# untitled_revisi.net
KiCad netlist of a schematic drawn in EAGLE
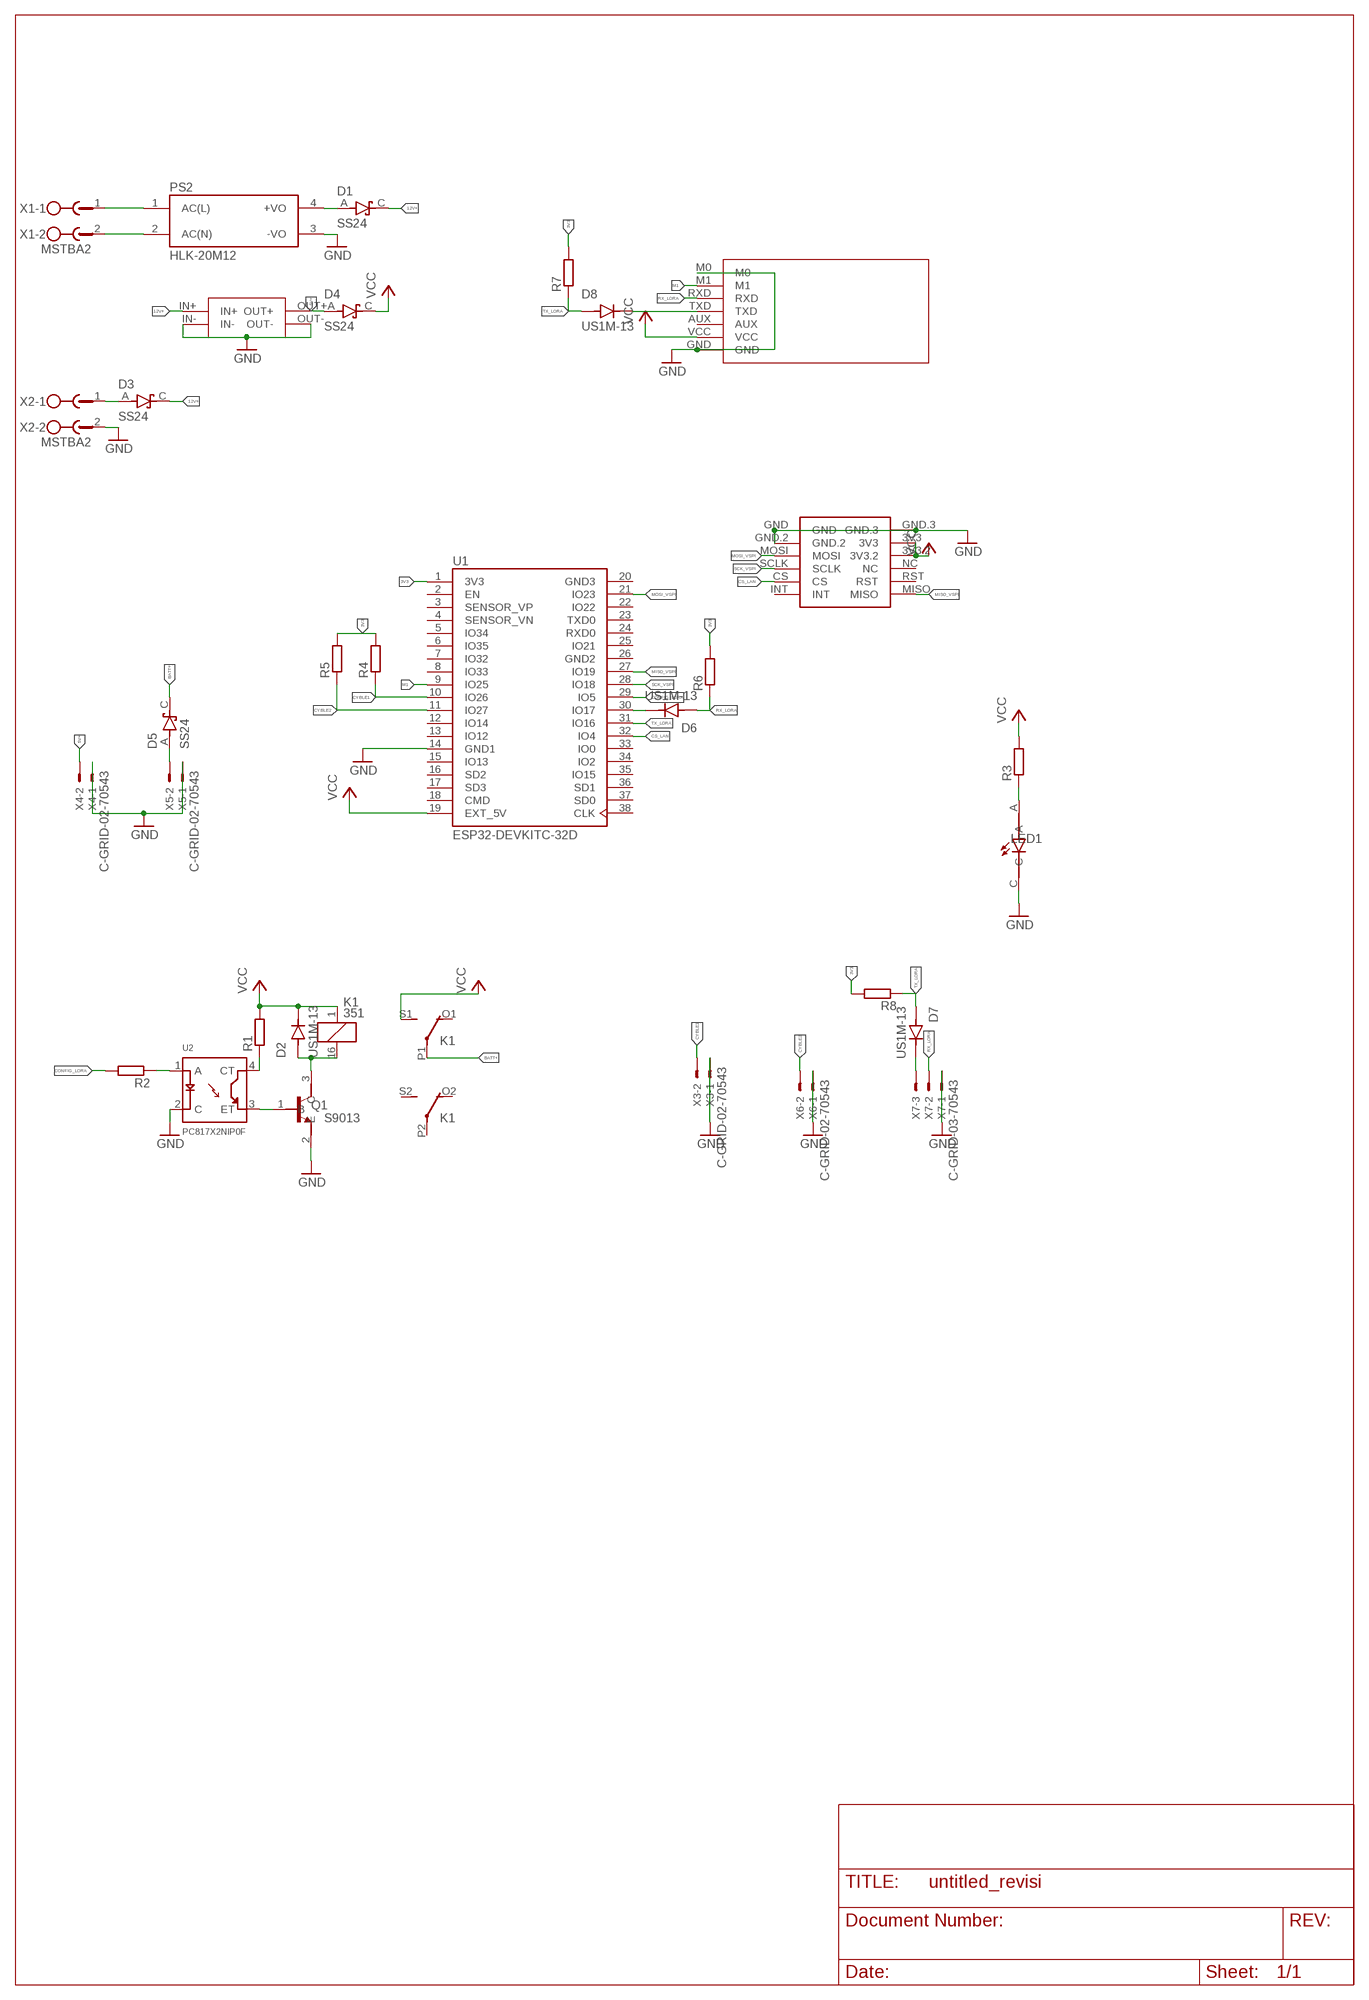
[diagram p0: schematic, sheet 1]

(export (version "E")
  (design (tool "Eeschema 10.0.6"))
  (components
    (comp (ref "D1")
      (value "SS24")
      (footprint "eagle-import:DIOM5336X265N")
      (fields (field (name "MF") "ON Semiconductor"))
      (libsource (lib "eagle-import") (part "SS24"))
    )
    (comp (ref "D2")
      (value "US1M-13")
      (footprint "eagle-import:DIOM5226X240N")
      (fields (field (name "MF") "Diodes Incorporated"))
      (libsource (lib "eagle-import") (part "US1M-13"))
    )
    (comp (ref "D3")
      (value "SS24")
      (footprint "eagle-import:DIOM5336X265N")
      (fields (field (name "MF") "ON Semiconductor"))
      (libsource (lib "eagle-import") (part "SS24"))
    )
    (comp (ref "D4")
      (value "SS24")
      (footprint "eagle-import:DIOM5336X265N")
      (fields (field (name "MF") "ON Semiconductor"))
      (libsource (lib "eagle-import") (part "SS24"))
    )
    (comp (ref "D5")
      (value "SS24")
      (footprint "eagle-import:DIOM5336X265N")
      (fields (field (name "MF") "ON Semiconductor"))
      (libsource (lib "eagle-import") (part "SS24"))
    )
    (comp (ref "D6")
      (value "US1M-13")
      (footprint "eagle-import:DIOM5226X240N")
      (fields (field (name "MF") "Diodes Incorporated"))
      (libsource (lib "eagle-import") (part "US1M-13"))
    )
    (comp (ref "D7")
      (value "US1M-13")
      (footprint "eagle-import:DIOM5226X240N")
      (fields (field (name "MF") "Diodes Incorporated"))
      (libsource (lib "eagle-import") (part "US1M-13"))
    )
    (comp (ref "D8")
      (value "US1M-13")
      (footprint "eagle-import:DIOM5226X240N")
      (fields (field (name "MF") "Diodes Incorporated"))
      (libsource (lib "eagle-import") (part "US1M-13"))
    )
    (comp (ref "EBYTEE220-900T22D1")
      (value "EBYTEE220-900T22D")
      (footprint "eagle-import:EBYTEE220-900T22D")
      (libsource (lib "eagle-import") (part "EBYTEE220-900T22D"))
    )
    (comp (ref "K1")
      (value "351")
      (footprint "eagle-import:351")
      (libsource (lib "eagle-import") (part "351"))
    )
    (comp (ref "LED1")
      (value "SML-LXT0805IW-TR")
      (footprint "eagle-import:LEDC2012X120N")
      (fields (field (name "MF") "Lumex Opto/Components"))
      (libsource (lib "eagle-import") (part "SML-LXT0805IW-TR"))
    )
    (comp (ref "MINI1")
      (value "MINI560")
      (footprint "eagle-import:MINI560")
      (libsource (lib "eagle-import") (part "MINI560"))
    )
    (comp (ref "PS2")
      (value "HLK-20M12")
      (footprint "eagle-import:CONV_HLK-20M12")
      (fields (field (name "MF") "Hi-link"))
      (libsource (lib "eagle-import") (part "HLK-20M12"))
    )
    (comp (ref "Q1")
      (value "S9013")
      (footprint "eagle-import:SOT95P240X120-3N")
      (fields (field (name "MF") "JCET"))
      (libsource (lib "eagle-import") (part "S9013"))
    )
    (comp (ref "R1")
      (value "R-EU_R0805")
      (footprint "eagle-import:R0805")
      (libsource (lib "eagle-import") (part "R-EU_R0805"))
    )
    (comp (ref "R2")
      (value "R-EU_R0805")
      (footprint "eagle-import:R0805")
      (libsource (lib "eagle-import") (part "R-EU_R0805"))
    )
    (comp (ref "R3")
      (value "R-EU_R0805")
      (footprint "eagle-import:R0805")
      (libsource (lib "eagle-import") (part "R-EU_R0805"))
    )
    (comp (ref "R4")
      (value "R-EU_R0805")
      (footprint "eagle-import:R0805")
      (libsource (lib "eagle-import") (part "R-EU_R0805"))
    )
    (comp (ref "R5")
      (value "R-EU_R0805")
      (footprint "eagle-import:R0805")
      (libsource (lib "eagle-import") (part "R-EU_R0805"))
    )
    (comp (ref "R6")
      (value "R-EU_R0805")
      (footprint "eagle-import:R0805")
      (libsource (lib "eagle-import") (part "R-EU_R0805"))
    )
    (comp (ref "R7")
      (value "R-EU_R0805")
      (footprint "eagle-import:R0805")
      (libsource (lib "eagle-import") (part "R-EU_R0805"))
    )
    (comp (ref "R8")
      (value "R-EU_R0805")
      (footprint "eagle-import:R0805")
      (libsource (lib "eagle-import") (part "R-EU_R0805"))
    )
    (comp (ref "U$1")
      (value "MINI_W5500")
      (footprint "eagle-import:MINI_W5500")
      (libsource (lib "eagle-import") (part "MINI_W5500"))
    )
    (comp (ref "U1")
      (value "ESP32-DEVKITC-32D")
      (footprint "eagle-import:MODULE_ESP32-DEVKITC-32D")
      (fields (field (name "MF") "Espressif Systems"))
      (libsource (lib "eagle-import") (part "ESP32-DEVKITC-32D"))
    )
    (comp (ref "U2")
      (value "PC817X2NIP0F")
      (footprint "eagle-import:SOT254P975X400-4N")
      (fields (field (name "MF") "Sharp Microelectronics"))
      (libsource (lib "eagle-import") (part "PC817X2NIP0F"))
    )
    (comp (ref "X1")
      (value "MSTBA2")
      (footprint "eagle-import:MSTBA2")
      (fields (field (name "MF") "FARNELL") (field (name "MPN") "1757242"))
      (libsource (lib "eagle-import") (part "MSTBA2"))
    )
    (comp (ref "X2")
      (value "MSTBA2")
      (footprint "eagle-import:MSTBA2")
      (fields (field (name "MF") "FARNELL") (field (name "MPN") "1757242"))
      (libsource (lib "eagle-import") (part "MSTBA2"))
    )
    (comp (ref "X3")
      (value "C-GRID-02-70543")
      (footprint "eagle-import:70543-02")
      (fields (field (name "MF") "MOLEX"))
      (libsource (lib "eagle-import") (part "C-GRID-02-70543"))
    )
    (comp (ref "X4")
      (value "C-GRID-02-70543")
      (footprint "eagle-import:70543-02")
      (fields (field (name "MF") "MOLEX"))
      (libsource (lib "eagle-import") (part "C-GRID-02-70543"))
    )
    (comp (ref "X5")
      (value "C-GRID-02-70543")
      (footprint "eagle-import:70543-02")
      (fields (field (name "MF") "MOLEX"))
      (libsource (lib "eagle-import") (part "C-GRID-02-70543"))
    )
    (comp (ref "X6")
      (value "C-GRID-02-70543")
      (footprint "eagle-import:70543-02")
      (fields (field (name "MF") "MOLEX"))
      (libsource (lib "eagle-import") (part "C-GRID-02-70543"))
    )
    (comp (ref "X7")
      (value "C-GRID-03-70543")
      (footprint "eagle-import:70543-03")
      (fields (field (name "MF") "MOLEX"))
      (libsource (lib "eagle-import") (part "C-GRID-03-70543"))
    )
  )
  (nets
    (net (code "1") (name "/GND2") (class "Default")
      (node (ref "U1") (pin "26") (pinfunction "GND2_26") (pintype "power_in"))
    )
    (net (code "2") (name "/GND3") (class "Default")
      (node (ref "U1") (pin "20") (pinfunction "GND3_20") (pintype "power_in"))
    )
    (net (code "3") (name "3V3") (class "Default")
      (node (ref "R4") (pin "2") (pinfunction "2_2") (pintype "passive"))
      (node (ref "R5") (pin "2") (pinfunction "2_2") (pintype "passive"))
      (node (ref "R6") (pin "2") (pinfunction "2_2") (pintype "passive"))
      (node (ref "R7") (pin "2") (pinfunction "2_2") (pintype "passive"))
      (node (ref "R8") (pin "2") (pinfunction "2_2") (pintype "passive"))
      (node (ref "U1") (pin "1") (pinfunction "3V3_1") (pintype "power_in"))
    )
    (net (code "4") (name "5V+") (class "Default")
      (node (ref "D4") (pin "A") (pinfunction "A_A") (pintype "passive"))
      (node (ref "MINI1") (pin "OUT+") (pinfunction "OUT+_OUT+") (pintype "bidirectional"))
      (node (ref "X4") (pin "2") (pinfunction "S_2") (pintype "passive"))
    )
    (net (code "5") (name "12V+") (class "Default")
      (node (ref "D1") (pin "C") (pinfunction "K_C") (pintype "passive"))
      (node (ref "D3") (pin "C") (pinfunction "K_C") (pintype "passive"))
      (node (ref "MINI1") (pin "IN+") (pinfunction "IN+_IN+") (pintype "bidirectional"))
    )
    (net (code "6") (name "BATT+") (class "Default")
      (node (ref "D5") (pin "C") (pinfunction "K_C") (pintype "passive"))
      (node (ref "K1") (pin "P1") (pinfunction "P_P1") (pintype "passive"))
    )
    (net (code "7") (name "CONFIG_LORA") (class "Default")
      (node (ref "R2") (pin "2") (pinfunction "2_2") (pintype "passive"))
      (node (ref "U1") (pin "29") (pinfunction "IO5_29") (pintype "bidirectional"))
    )
    (net (code "8") (name "CS_LAN") (class "Default")
      (node (ref "U$1") (pin "CS") (pinfunction "CS_CS") (pintype "bidirectional"))
      (node (ref "U1") (pin "32") (pinfunction "IO4_32") (pintype "bidirectional"))
    )
    (net (code "9") (name "CYBLE1") (class "Default")
      (node (ref "R4") (pin "1") (pinfunction "1_1") (pintype "passive"))
      (node (ref "U1") (pin "10") (pinfunction "IO26_10") (pintype "bidirectional"))
      (node (ref "X3") (pin "2") (pinfunction "S_2") (pintype "passive"))
    )
    (net (code "10") (name "CYBLE2") (class "Default")
      (node (ref "R5") (pin "1") (pinfunction "1_1") (pintype "passive"))
      (node (ref "U1") (pin "11") (pinfunction "IO27_11") (pintype "bidirectional"))
      (node (ref "X6") (pin "2") (pinfunction "S_2") (pintype "passive"))
    )
    (net (code "11") (name "GND") (class "Default")
      (node (ref "EBYTEE220-900T22D1") (pin "GND") (pinfunction "GND_GND") (pintype "bidirectional"))
      (node (ref "EBYTEE220-900T22D1") (pin "M0") (pinfunction "M0_M0") (pintype "bidirectional"))
      (node (ref "LED1") (pin "C") (pinfunction "C_C") (pintype "passive"))
      (node (ref "MINI1") (pin "IN-") (pinfunction "IN-_IN-") (pintype "bidirectional"))
      (node (ref "MINI1") (pin "OUT-") (pinfunction "OUT-_OUT-") (pintype "bidirectional"))
      (node (ref "PS2") (pin "3") (pinfunction "-VO_3") (pintype "output"))
      (node (ref "Q1") (pin "2") (pinfunction "E_2") (pintype "passive"))
      (node (ref "U$1") (pin "GND") (pinfunction "GND_GND") (pintype "bidirectional"))
      (node (ref "U$1") (pin "GND.2") (pinfunction "GND.2_GND.2") (pintype "bidirectional"))
      (node (ref "U$1") (pin "GND.3") (pinfunction "GND.3_GND.3") (pintype "bidirectional"))
      (node (ref "U1") (pin "14") (pinfunction "GND1_14") (pintype "power_in"))
      (node (ref "U2") (pin "2") (pinfunction "C_2") (pintype "passive"))
      (node (ref "X2") (pin "2") (pinfunction "1_2") (pintype "passive"))
      (node (ref "X3") (pin "1") (pinfunction "S_1") (pintype "passive"))
      (node (ref "X4") (pin "1") (pinfunction "S_1") (pintype "passive"))
      (node (ref "X5") (pin "1") (pinfunction "S_1") (pintype "passive"))
      (node (ref "X6") (pin "1") (pinfunction "S_1") (pintype "passive"))
      (node (ref "X7") (pin "1") (pinfunction "S_1") (pintype "passive"))
    )
    (net (code "12") (name "M1") (class "Default")
      (node (ref "EBYTEE220-900T22D1") (pin "M1") (pinfunction "M1_M1") (pintype "bidirectional"))
      (node (ref "U1") (pin "9") (pinfunction "IO25_9") (pintype "bidirectional"))
    )
    (net (code "13") (name "MISO_VSPI") (class "Default")
      (node (ref "U$1") (pin "MISO") (pinfunction "MISO_MISO") (pintype "bidirectional"))
      (node (ref "U1") (pin "27") (pinfunction "IO19_27") (pintype "bidirectional"))
    )
    (net (code "14") (name "MOSI_VSPI") (class "Default")
      (node (ref "U$1") (pin "MOSI") (pinfunction "MOSI_MOSI") (pintype "bidirectional"))
      (node (ref "U1") (pin "21") (pinfunction "IO23_21") (pintype "bidirectional"))
    )
    (net (code "15") (name "Net-(D3-PadA)") (class "Default")
      (node (ref "D3") (pin "A") (pinfunction "A_A") (pintype "passive"))
      (node (ref "X2") (pin "1") (pinfunction "1_1") (pintype "passive"))
    )
    (net (code "16") (name "Net-(D6-K)") (class "Default")
      (node (ref "D6") (pin "C") (pinfunction "K_C") (pintype "passive"))
      (node (ref "U1") (pin "30") (pinfunction "IO17_30") (pintype "bidirectional"))
    )
    (net (code "17") (name "Net-(D7-K)") (class "Default")
      (node (ref "D7") (pin "C") (pinfunction "K_C") (pintype "passive"))
      (node (ref "X7") (pin "3") (pinfunction "S_3") (pintype "passive"))
    )
    (net (code "18") (name "Net-(D8-K)") (class "Default")
      (node (ref "D8") (pin "C") (pinfunction "K_C") (pintype "passive"))
      (node (ref "EBYTEE220-900T22D1") (pin "TXD") (pinfunction "TXD_TXD") (pintype "bidirectional"))
    )
    (net (code "19") (name "Net-(K1A-2)") (class "Default")
      (node (ref "D2") (pin "A") (pinfunction "A_A") (pintype "passive"))
      (node (ref "K1") (pin "16") (pinfunction "2_16") (pintype "passive"))
      (node (ref "Q1") (pin "3") (pinfunction "C_3") (pintype "passive"))
    )
    (net (code "20") (name "Net-(LED1-PadA)") (class "Default")
      (node (ref "LED1") (pin "A") (pinfunction "A_A") (pintype "passive"))
      (node (ref "R3") (pin "1") (pinfunction "1_1") (pintype "passive"))
    )
    (net (code "21") (name "Net-(PS2-+VO)") (class "Default")
      (node (ref "D1") (pin "A") (pinfunction "A_A") (pintype "passive"))
      (node (ref "PS2") (pin "4") (pinfunction "+VO_4") (pintype "output"))
    )
    (net (code "22") (name "Net-(PS2-AC(L))") (class "Default")
      (node (ref "PS2") (pin "1") (pinfunction "AC(L)_1") (pintype "input"))
      (node (ref "X1") (pin "1") (pinfunction "1_1") (pintype "passive"))
    )
    (net (code "23") (name "Net-(PS2-AC(N))") (class "Default")
      (node (ref "PS2") (pin "2") (pinfunction "AC(N)_2") (pintype "input"))
      (node (ref "X1") (pin "2") (pinfunction "1_2") (pintype "passive"))
    )
    (net (code "24") (name "Net-(Q1-B)") (class "Default")
      (node (ref "Q1") (pin "1") (pinfunction "B_1") (pintype "passive"))
      (node (ref "U2") (pin "3") (pinfunction "ET_3") (pintype "passive"))
    )
    (net (code "25") (name "Net-(U2-A)") (class "Default")
      (node (ref "R2") (pin "1") (pinfunction "1_1") (pintype "passive"))
      (node (ref "U2") (pin "1") (pinfunction "A_1") (pintype "passive"))
    )
    (net (code "26") (name "Net-(U2-CT)") (class "Default")
      (node (ref "R1") (pin "1") (pinfunction "1_1") (pintype "passive"))
      (node (ref "U2") (pin "4") (pinfunction "CT_4") (pintype "passive"))
    )
    (net (code "27") (name "Net-(X5B-S)") (class "Default")
      (node (ref "D5") (pin "A") (pinfunction "A_A") (pintype "passive"))
      (node (ref "X5") (pin "2") (pinfunction "S_2") (pintype "passive"))
    )
    (net (code "28") (name "RX_LORA") (class "Default")
      (node (ref "D6") (pin "A") (pinfunction "A_A") (pintype "passive"))
      (node (ref "EBYTEE220-900T22D1") (pin "RXD") (pinfunction "RXD_RXD") (pintype "bidirectional"))
      (node (ref "R6") (pin "1") (pinfunction "1_1") (pintype "passive"))
      (node (ref "X7") (pin "2") (pinfunction "S_2") (pintype "passive"))
    )
    (net (code "29") (name "SCK_VSPI") (class "Default")
      (node (ref "U$1") (pin "SCLK") (pinfunction "SCLK_SCLK") (pintype "bidirectional"))
      (node (ref "U1") (pin "28") (pinfunction "IO18_28") (pintype "bidirectional"))
    )
    (net (code "30") (name "TX_LORA") (class "Default")
      (node (ref "D7") (pin "A") (pinfunction "A_A") (pintype "passive"))
      (node (ref "D8") (pin "A") (pinfunction "A_A") (pintype "passive"))
      (node (ref "R7") (pin "1") (pinfunction "1_1") (pintype "passive"))
      (node (ref "R8") (pin "1") (pinfunction "1_1") (pintype "passive"))
      (node (ref "U1") (pin "31") (pinfunction "IO16_31") (pintype "bidirectional"))
    )
    (net (code "31") (name "VCC") (class "Default")
      (node (ref "D2") (pin "C") (pinfunction "K_C") (pintype "passive"))
      (node (ref "D4") (pin "C") (pinfunction "K_C") (pintype "passive"))
      (node (ref "EBYTEE220-900T22D1") (pin "VCC") (pinfunction "VCC_VCC") (pintype "bidirectional"))
      (node (ref "K1") (pin "1") (pinfunction "1_1") (pintype "passive"))
      (node (ref "K1") (pin "S1") (pinfunction "S_S1") (pintype "passive"))
      (node (ref "R1") (pin "2") (pinfunction "2_2") (pintype "passive"))
      (node (ref "R3") (pin "2") (pinfunction "2_2") (pintype "passive"))
      (node (ref "U$1") (pin "3V3") (pinfunction "3V3_3V3") (pintype "bidirectional"))
      (node (ref "U$1") (pin "3V3.2") (pinfunction "3V3.2_3V3.2") (pintype "bidirectional"))
      (node (ref "U1") (pin "19") (pinfunction "EXT_5V_19") (pintype "power_in"))
    )
    (net (code "32") (name "unconnected-(EBYTEE220-900T22D1-PadAUX)") (class "Default")
      (node (ref "EBYTEE220-900T22D1") (pin "AUX") (pinfunction "AUX_AUX") (pintype "bidirectional"))
    )
    (net (code "33") (name "unconnected-(K1B-O-PadO1)") (class "Default")
      (node (ref "K1") (pin "O1") (pinfunction "O_O1") (pintype "passive"))
    )
    (net (code "34") (name "unconnected-(K1C-O-PadO2)") (class "Default")
      (node (ref "K1") (pin "O2") (pinfunction "O_O2") (pintype "passive"))
    )
    (net (code "35") (name "unconnected-(K1C-P-PadP2)") (class "Default")
      (node (ref "K1") (pin "P2") (pinfunction "P_P2") (pintype "passive"))
    )
    (net (code "36") (name "unconnected-(K1C-S-PadS2)") (class "Default")
      (node (ref "K1") (pin "S2") (pinfunction "S_S2") (pintype "passive"))
    )
    (net (code "37") (name "unconnected-(U$1-PadINT)") (class "Default")
      (node (ref "U$1") (pin "INT") (pinfunction "INT_INT") (pintype "bidirectional"))
    )
    (net (code "38") (name "unconnected-(U$1-PadNC)") (class "Default")
      (node (ref "U$1") (pin "NC") (pinfunction "NC_NC") (pintype "bidirectional"))
    )
    (net (code "39") (name "unconnected-(U$1-PadRST)") (class "Default")
      (node (ref "U$1") (pin "RST") (pinfunction "RST_RST") (pintype "bidirectional"))
    )
    (net (code "40") (name "unconnected-(U1-CLK-Pad38)") (class "Default")
      (node (ref "U1") (pin "38") (pinfunction "CLK_38") (pintype "input"))
    )
    (net (code "41") (name "unconnected-(U1-CMD-Pad18)") (class "Default")
      (node (ref "U1") (pin "18") (pinfunction "CMD_18") (pintype "bidirectional"))
    )
    (net (code "42") (name "unconnected-(U1-EN-Pad2)") (class "Default")
      (node (ref "U1") (pin "2") (pinfunction "EN_2") (pintype "input"))
    )
    (net (code "43") (name "unconnected-(U1-IO0-Pad33)") (class "Default")
      (node (ref "U1") (pin "33") (pinfunction "IO0_33") (pintype "bidirectional"))
    )
    (net (code "44") (name "unconnected-(U1-IO2-Pad34)") (class "Default")
      (node (ref "U1") (pin "34") (pinfunction "IO2_34") (pintype "bidirectional"))
    )
    (net (code "45") (name "unconnected-(U1-IO12-Pad13)") (class "Default")
      (node (ref "U1") (pin "13") (pinfunction "IO12_13") (pintype "bidirectional"))
    )
    (net (code "46") (name "unconnected-(U1-IO13-Pad15)") (class "Default")
      (node (ref "U1") (pin "15") (pinfunction "IO13_15") (pintype "bidirectional"))
    )
    (net (code "47") (name "unconnected-(U1-IO14-Pad12)") (class "Default")
      (node (ref "U1") (pin "12") (pinfunction "IO14_12") (pintype "bidirectional"))
    )
    (net (code "48") (name "unconnected-(U1-IO15-Pad35)") (class "Default")
      (node (ref "U1") (pin "35") (pinfunction "IO15_35") (pintype "bidirectional"))
    )
    (net (code "49") (name "unconnected-(U1-IO21-Pad25)") (class "Default")
      (node (ref "U1") (pin "25") (pinfunction "IO21_25") (pintype "bidirectional"))
    )
    (net (code "50") (name "unconnected-(U1-IO22-Pad22)") (class "Default")
      (node (ref "U1") (pin "22") (pinfunction "IO22_22") (pintype "bidirectional"))
    )
    (net (code "51") (name "unconnected-(U1-IO32-Pad7)") (class "Default")
      (node (ref "U1") (pin "7") (pinfunction "IO32_7") (pintype "bidirectional"))
    )
    (net (code "52") (name "unconnected-(U1-IO33-Pad8)") (class "Default")
      (node (ref "U1") (pin "8") (pinfunction "IO33_8") (pintype "bidirectional"))
    )
    (net (code "53") (name "unconnected-(U1-IO34-Pad5)") (class "Default")
      (node (ref "U1") (pin "5") (pinfunction "IO34_5") (pintype "bidirectional"))
    )
    (net (code "54") (name "unconnected-(U1-IO35-Pad6)") (class "Default")
      (node (ref "U1") (pin "6") (pinfunction "IO35_6") (pintype "bidirectional"))
    )
    (net (code "55") (name "unconnected-(U1-RXD0-Pad24)") (class "Default")
      (node (ref "U1") (pin "24") (pinfunction "RXD0_24") (pintype "input"))
    )
    (net (code "56") (name "unconnected-(U1-SD0-Pad37)") (class "Default")
      (node (ref "U1") (pin "37") (pinfunction "SD0_37") (pintype "bidirectional"))
    )
    (net (code "57") (name "unconnected-(U1-SD1-Pad36)") (class "Default")
      (node (ref "U1") (pin "36") (pinfunction "SD1_36") (pintype "bidirectional"))
    )
    (net (code "58") (name "unconnected-(U1-SD2-Pad16)") (class "Default")
      (node (ref "U1") (pin "16") (pinfunction "SD2_16") (pintype "bidirectional"))
    )
    (net (code "59") (name "unconnected-(U1-SD3-Pad17)") (class "Default")
      (node (ref "U1") (pin "17") (pinfunction "SD3_17") (pintype "bidirectional"))
    )
    (net (code "60") (name "unconnected-(U1-SENSOR_VN-Pad4)") (class "Default")
      (node (ref "U1") (pin "4") (pinfunction "SENSOR_VN_4") (pintype "input"))
    )
    (net (code "61") (name "unconnected-(U1-SENSOR_VP-Pad3)") (class "Default")
      (node (ref "U1") (pin "3") (pinfunction "SENSOR_VP_3") (pintype "input"))
    )
    (net (code "62") (name "unconnected-(U1-TXD0-Pad23)") (class "Default")
      (node (ref "U1") (pin "23") (pinfunction "TXD0_23") (pintype "output"))
    )
  )
)
